# GSM.net
KiCad netlist of a schematic drawn in Altium Designer
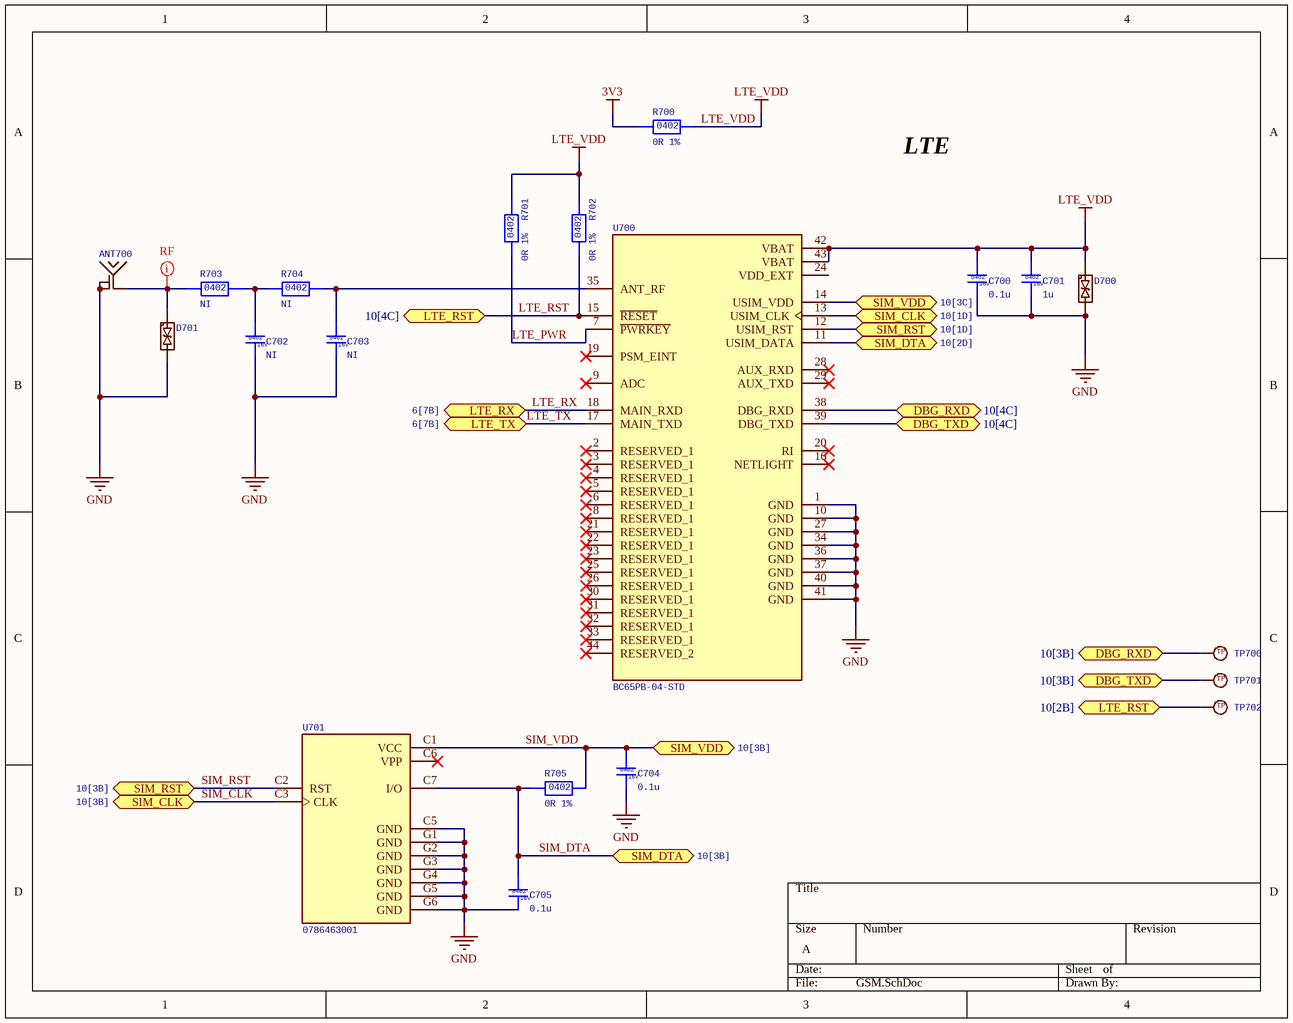
[diagram p0: GSM.SchDoc]

(export (version "E")
  (design (tool "Eeschema 10.0.6"))
  (components
    (comp (ref "ANT700")
      (value "2337019-1")
      (footprint "2337019-1")
      (description "UMCC MICRO-COAX RECEPTACLE, GEN")
      (libsource (lib "Hw_Lib") (part "2337019-1"))
    )
    (comp (ref "C700")
      (value "0.1u")
      (footprint "CAP0402")
      (fields
        (field (name "MANUFACTURER") "Murata")
        (field (name "MANUFACTURER PART NUMBER") "GRM155R71C104KA88J")
      )
      (libsource (lib "Hw_Lib") (part "C_0402_0.1u"))
    )
    (comp (ref "C701")
      (value "1u")
      (footprint "CAP0402")
      (fields
        (field (name "MANUFACTURER") "Taiyo Yuden")
        (field (name "MANUFACTURER PART NUMBER") "EMK105BJ105KV-F")
      )
      (libsource (lib "Hw_Lib") (part "C_0402_1u"))
    )
    (comp (ref "C702")
      (value "NI")
      (footprint "CAP0402")
      (fields
        (field (name "MANUFACTURER") "Murata")
        (field (name "MANUFACTURER PART NUMBER") "GRM155R71C104KA88J")
      )
      (libsource (lib "Hw_Lib") (part "C_0402_0.1u"))
    )
    (comp (ref "C703")
      (value "NI")
      (footprint "CAP0402")
      (fields
        (field (name "MANUFACTURER") "Murata")
        (field (name "MANUFACTURER PART NUMBER") "GRM155R71C104KA88J")
      )
      (libsource (lib "Hw_Lib") (part "C_0402_0.1u"))
    )
    (comp (ref "C704")
      (value "0.1u")
      (footprint "CAP0402")
      (fields
        (field (name "MANUFACTURER") "Murata")
        (field (name "MANUFACTURER PART NUMBER") "GRM155R71C104KA88J")
      )
      (libsource (lib "Hw_Lib") (part "C_0402_0.1u"))
    )
    (comp (ref "C705")
      (value "0.1u")
      (footprint "CAP0402")
      (fields
        (field (name "MANUFACTURER") "Murata")
        (field (name "MANUFACTURER PART NUMBER") "GRM155R71C104KA88J")
      )
      (libsource (lib "Hw_Lib") (part "C_0402_0.1u"))
    )
    (comp (ref "D700")
      (value "DESD3V3S1BL-7B")
      (footprint "DESD3V3S1BL-7B")
      (description "Trans Voltage Suppressor Diode, 35W, 3.3V V(RWM), Bidirectional, 1 Element, Silicon")
      (fields (field (name "MANUFACTURER") "Diodes"))
      (libsource (lib "Hw_Lib") (part "DESD3V3S1BL-7B"))
    )
    (comp (ref "D701")
      (value "DESD3V3S1BL-7B")
      (footprint "DESD3V3S1BL-7B")
      (description "Trans Voltage Suppressor Diode, 35W, 3.3V V(RWM), Bidirectional, 1 Element, Silicon")
      (fields (field (name "MANUFACTURER") "Diodes"))
      (libsource (lib "Hw_Lib") (part "DESD3V3S1BL-7B"))
    )
    (comp (ref "R700")
      (value "0R 1%")
      (footprint "RES0402")
      (description "Metal Glaze/thick Film, 0.0625W, 0ohm, Surface Mount, 0402")
      (fields
        (field (name "MANUFACTURER") "Yageo")
        (field (name "MANUFACTURER PART NUMBER") "RC0402JR-070RL")
      )
      (libsource (lib "Hw_Lib") (part "R_0402_0R"))
    )
    (comp (ref "R701")
      (value "0R 1%")
      (footprint "RES0402")
      (description "Metal Glaze/thick Film, 0.0625W, 0ohm, Surface Mount, 0402")
      (fields
        (field (name "MANUFACTURER") "Yageo")
        (field (name "MANUFACTURER PART NUMBER") "RC0402JR-070RL")
      )
      (libsource (lib "Hw_Lib") (part "R_0402_0R"))
    )
    (comp (ref "R702")
      (value "0R 1%")
      (footprint "RES0402")
      (description "Metal Glaze/thick Film, 0.0625W, 0ohm, Surface Mount, 0402")
      (fields
        (field (name "MANUFACTURER") "Yageo")
        (field (name "MANUFACTURER PART NUMBER") "RC0402JR-070RL")
      )
      (libsource (lib "Hw_Lib") (part "R_0402_0R"))
    )
    (comp (ref "R703")
      (value "NI")
      (footprint "RES0402")
      (description "Metal Glaze/thick Film, 0.0625W, 0ohm, Surface Mount, 0402")
      (fields
        (field (name "MANUFACTURER") "Yageo")
        (field (name "MANUFACTURER PART NUMBER") "RC0402JR-070RL")
      )
      (libsource (lib "Hw_Lib") (part "R_0402_0R"))
    )
    (comp (ref "R704")
      (value "NI")
      (footprint "RES0402")
      (description "Metal Glaze/thick Film, 0.0625W, 0ohm, Surface Mount, 0402")
      (fields
        (field (name "MANUFACTURER") "Yageo")
        (field (name "MANUFACTURER PART NUMBER") "RC0402JR-070RL")
      )
      (libsource (lib "Hw_Lib") (part "R_0402_0R"))
    )
    (comp (ref "R705")
      (value "0R 1%")
      (footprint "RES0402")
      (description "Metal Glaze/thick Film, 0.0625W, 0ohm, Surface Mount, 0402")
      (fields
        (field (name "MANUFACTURER") "Yageo")
        (field (name "MANUFACTURER PART NUMBER") "RC0402JR-070RL")
      )
      (libsource (lib "Hw_Lib") (part "R_0402_0R"))
    )
    (comp (ref "TP700")
      (value "TP")
      (footprint "TP")
      (description "Test Point")
      (libsource (lib "Hw_Lib") (part "TP"))
    )
    (comp (ref "TP701")
      (value "TP")
      (footprint "TP")
      (description "Test Point")
      (libsource (lib "Hw_Lib") (part "TP"))
    )
    (comp (ref "TP702")
      (value "TP")
      (footprint "TP")
      (description "Test Point")
      (libsource (lib "Hw_Lib") (part "TP"))
    )
    (comp (ref "U700")
      (value "BC65PB-04-STD")
      (footprint "BC65PB-04-STD")
      (fields (field (name "MANUFACTURER") "Quectel Wireless Solutions"))
      (libsource (lib "Hw_Lib") (part "BC65PB-04-STD"))
    )
    (comp (ref "U701")
      (value "0786463001")
      (footprint "0786463001")
      (description "PCB Connector")
      (fields (field (name "MANUFACTURER") "Molex"))
      (libsource (lib "Hw_Lib") (part "0786463001"))
    )
  )
  (nets
    (net (code "1") (name "/DBG_RXD") (class "Default")
      (node (ref "TP700") (pin "1") (pinfunction "1_1") (pintype "passive"))
      (node (ref "U700") (pin "38") (pinfunction "DBG_RXD_38") (pintype "open_collector"))
    )
    (net (code "2") (name "/DBG_TXD") (class "Default")
      (node (ref "TP701") (pin "1") (pinfunction "1_1") (pintype "passive"))
      (node (ref "U700") (pin "39") (pinfunction "DBG_TXD_39") (pintype "open_collector"))
    )
    (net (code "3") (name "/LTE_PWR") (class "Default")
      (node (ref "R701") (pin "1") (pinfunction "1_1") (pintype "passive"))
      (node (ref "U700") (pin "7") (pinfunction "~{PWRKEY}_7") (pintype "open_collector"))
    )
    (net (code "4") (name "/LTE_RST") (class "Default")
      (node (ref "R702") (pin "1") (pinfunction "1_1") (pintype "passive"))
      (node (ref "TP702") (pin "1") (pinfunction "1_1") (pintype "passive"))
      (node (ref "U700") (pin "15") (pinfunction "~{RESET}_15") (pintype "open_collector"))
    )
    (net (code "5") (name "/LTE_RX") (class "Default")
      (node (ref "U700") (pin "18") (pinfunction "MAIN_RXD_18") (pintype "open_collector"))
    )
    (net (code "6") (name "/LTE_TX") (class "Default")
      (node (ref "U700") (pin "17") (pinfunction "MAIN_TXD_17") (pintype "open_collector"))
    )
    (net (code "7") (name "/SIM_CLK") (class "Default")
      (node (ref "U700") (pin "13") (pinfunction "USIM_CLK_13") (pintype "open_collector"))
      (node (ref "U701") (pin "C3") (pinfunction "CLK_C3") (pintype "open_collector"))
    )
    (net (code "8") (name "/SIM_DTA") (class "Default")
      (node (ref "C705") (pin "1") (pinfunction "1_1") (pintype "passive"))
      (node (ref "R705") (pin "1") (pinfunction "1_1") (pintype "passive"))
      (node (ref "U700") (pin "11") (pinfunction "USIM_DATA_11") (pintype "open_collector"))
      (node (ref "U701") (pin "C7") (pinfunction "I/O_C7") (pintype "open_collector"))
    )
    (net (code "9") (name "/SIM_RST") (class "Default")
      (node (ref "U700") (pin "12") (pinfunction "USIM_RST_12") (pintype "open_collector"))
      (node (ref "U701") (pin "C2") (pinfunction "RST_C2") (pintype "open_collector"))
    )
    (net (code "10") (name "/SIM_VDD") (class "Default")
      (node (ref "C704") (pin "1") (pinfunction "1_1") (pintype "passive"))
      (node (ref "R705") (pin "2") (pinfunction "2_2") (pintype "passive"))
      (node (ref "U700") (pin "14") (pinfunction "USIM_VDD_14") (pintype "open_collector"))
      (node (ref "U701") (pin "C1") (pinfunction "VCC_C1") (pintype "open_collector"))
    )
    (net (code "11") (name "3V3") (class "Default")
      (node (ref "R700") (pin "1") (pinfunction "1_1") (pintype "passive"))
    )
    (net (code "12") (name "GND") (class "Default")
      (node (ref "ANT700") (pin "G1") (pinfunction "GND_G1") (pintype "open_collector"))
      (node (ref "ANT700") (pin "G2") (pinfunction "GND_G2") (pintype "open_collector"))
      (node (ref "C700") (pin "2") (pinfunction "2_2") (pintype "passive"))
      (node (ref "C701") (pin "2") (pinfunction "2_2") (pintype "passive"))
      (node (ref "C702") (pin "2") (pinfunction "2_2") (pintype "passive"))
      (node (ref "C703") (pin "2") (pinfunction "2_2") (pintype "passive"))
      (node (ref "C704") (pin "2") (pinfunction "2_2") (pintype "passive"))
      (node (ref "C705") (pin "2") (pinfunction "2_2") (pintype "passive"))
      (node (ref "D700") (pin "2") (pinfunction "2_2") (pintype "passive"))
      (node (ref "D701") (pin "2") (pinfunction "2_2") (pintype "passive"))
      (node (ref "U700") (pin "1") (pinfunction "GND_1") (pintype "open_collector"))
      (node (ref "U700") (pin "10") (pinfunction "GND_10") (pintype "open_collector"))
      (node (ref "U700") (pin "27") (pinfunction "GND_27") (pintype "open_collector"))
      (node (ref "U700") (pin "34") (pinfunction "GND_34") (pintype "open_collector"))
      (node (ref "U700") (pin "36") (pinfunction "GND_36") (pintype "open_collector"))
      (node (ref "U700") (pin "37") (pinfunction "GND_37") (pintype "open_collector"))
      (node (ref "U700") (pin "40") (pinfunction "GND_40") (pintype "open_collector"))
      (node (ref "U700") (pin "41") (pinfunction "GND_41") (pintype "open_collector"))
      (node (ref "U701") (pin "C5") (pinfunction "GND_C5") (pintype "open_collector"))
      (node (ref "U701") (pin "G1") (pinfunction "GND_G1") (pintype "open_collector"))
      (node (ref "U701") (pin "G2") (pinfunction "GND_G2") (pintype "open_collector"))
      (node (ref "U701") (pin "G3") (pinfunction "GND_G3") (pintype "open_collector"))
      (node (ref "U701") (pin "G4") (pinfunction "GND_G4") (pintype "open_collector"))
      (node (ref "U701") (pin "G5") (pinfunction "GND_G5") (pintype "open_collector"))
      (node (ref "U701") (pin "G6") (pinfunction "GND_G6") (pintype "open_collector"))
    )
    (net (code "13") (name "LTE_VDD") (class "Default")
      (node (ref "C700") (pin "1") (pinfunction "1_1") (pintype "passive"))
      (node (ref "C701") (pin "1") (pinfunction "1_1") (pintype "passive"))
      (node (ref "D700") (pin "1") (pinfunction "1_1") (pintype "passive"))
      (node (ref "R700") (pin "2") (pinfunction "2_2") (pintype "passive"))
      (node (ref "R701") (pin "2") (pinfunction "2_2") (pintype "passive"))
      (node (ref "R702") (pin "2") (pinfunction "2_2") (pintype "passive"))
      (node (ref "U700") (pin "42") (pinfunction "VBAT_42") (pintype "open_collector"))
      (node (ref "U700") (pin "43") (pinfunction "VBAT_43") (pintype "open_collector"))
    )
    (net (code "14") (name "Net-(ANT700-Pad1)") (class "Default")
      (node (ref "ANT700") (pin "1") (pinfunction "1_1") (pintype "passive"))
      (node (ref "D701") (pin "1") (pinfunction "1_1") (pintype "passive"))
      (node (ref "R703") (pin "1") (pinfunction "1_1") (pintype "passive"))
    )
    (net (code "15") (name "Net-(C702-Pad1)") (class "Default")
      (node (ref "C702") (pin "1") (pinfunction "1_1") (pintype "passive"))
      (node (ref "R703") (pin "2") (pinfunction "2_2") (pintype "passive"))
      (node (ref "R704") (pin "1") (pinfunction "1_1") (pintype "passive"))
    )
    (net (code "16") (name "Net-(U700-ANT_RF)") (class "Default")
      (node (ref "C703") (pin "1") (pinfunction "1_1") (pintype "passive"))
      (node (ref "R704") (pin "2") (pinfunction "2_2") (pintype "passive"))
      (node (ref "U700") (pin "35") (pinfunction "ANT_RF_35") (pintype "open_collector"))
    )
    (net (code "17") (name "unconnected-(U700-ADC-Pad9)") (class "Default")
      (node (ref "U700") (pin "9") (pinfunction "ADC_9") (pintype "open_collector+no_connect"))
    )
    (net (code "18") (name "unconnected-(U700-AUX_RXD-Pad28)") (class "Default")
      (node (ref "U700") (pin "28") (pinfunction "AUX_RXD_28") (pintype "open_collector+no_connect"))
    )
    (net (code "19") (name "unconnected-(U700-AUX_TXD-Pad29)") (class "Default")
      (node (ref "U700") (pin "29") (pinfunction "AUX_TXD_29") (pintype "open_collector+no_connect"))
    )
    (net (code "20") (name "unconnected-(U700-NETLIGHT-Pad16)") (class "Default")
      (node (ref "U700") (pin "16") (pinfunction "NETLIGHT_16") (pintype "open_collector+no_connect"))
    )
    (net (code "21") (name "unconnected-(U700-PSM_EINT-Pad19)") (class "Default")
      (node (ref "U700") (pin "19") (pinfunction "PSM_EINT_19") (pintype "open_collector+no_connect"))
    )
    (net (code "22") (name "unconnected-(U700-RESERVED_1-Pad2)") (class "Default")
      (node (ref "U700") (pin "2") (pinfunction "RESERVED_1_2") (pintype "open_collector+no_connect"))
    )
    (net (code "23") (name "unconnected-(U700-RESERVED_1-Pad3)") (class "Default")
      (node (ref "U700") (pin "3") (pinfunction "RESERVED_1_3") (pintype "open_collector+no_connect"))
    )
    (net (code "24") (name "unconnected-(U700-RESERVED_1-Pad4)") (class "Default")
      (node (ref "U700") (pin "4") (pinfunction "RESERVED_1_4") (pintype "open_collector+no_connect"))
    )
    (net (code "25") (name "unconnected-(U700-RESERVED_1-Pad5)") (class "Default")
      (node (ref "U700") (pin "5") (pinfunction "RESERVED_1_5") (pintype "open_collector+no_connect"))
    )
    (net (code "26") (name "unconnected-(U700-RESERVED_1-Pad6)") (class "Default")
      (node (ref "U700") (pin "6") (pinfunction "RESERVED_1_6") (pintype "open_collector+no_connect"))
    )
    (net (code "27") (name "unconnected-(U700-RESERVED_1-Pad8)") (class "Default")
      (node (ref "U700") (pin "8") (pinfunction "RESERVED_1_8") (pintype "open_collector+no_connect"))
    )
    (net (code "28") (name "unconnected-(U700-RESERVED_1-Pad21)") (class "Default")
      (node (ref "U700") (pin "21") (pinfunction "RESERVED_1_21") (pintype "open_collector+no_connect"))
    )
    (net (code "29") (name "unconnected-(U700-RESERVED_1-Pad22)") (class "Default")
      (node (ref "U700") (pin "22") (pinfunction "RESERVED_1_22") (pintype "open_collector+no_connect"))
    )
    (net (code "30") (name "unconnected-(U700-RESERVED_1-Pad23)") (class "Default")
      (node (ref "U700") (pin "23") (pinfunction "RESERVED_1_23") (pintype "open_collector+no_connect"))
    )
    (net (code "31") (name "unconnected-(U700-RESERVED_1-Pad25)") (class "Default")
      (node (ref "U700") (pin "25") (pinfunction "RESERVED_1_25") (pintype "open_collector+no_connect"))
    )
    (net (code "32") (name "unconnected-(U700-RESERVED_1-Pad26)") (class "Default")
      (node (ref "U700") (pin "26") (pinfunction "RESERVED_1_26") (pintype "open_collector+no_connect"))
    )
    (net (code "33") (name "unconnected-(U700-RESERVED_1-Pad30)") (class "Default")
      (node (ref "U700") (pin "30") (pinfunction "RESERVED_1_30") (pintype "open_collector+no_connect"))
    )
    (net (code "34") (name "unconnected-(U700-RESERVED_1-Pad31)") (class "Default")
      (node (ref "U700") (pin "31") (pinfunction "RESERVED_1_31") (pintype "open_collector+no_connect"))
    )
    (net (code "35") (name "unconnected-(U700-RESERVED_1-Pad32)") (class "Default")
      (node (ref "U700") (pin "32") (pinfunction "RESERVED_1_32") (pintype "open_collector+no_connect"))
    )
    (net (code "36") (name "unconnected-(U700-RESERVED_1-Pad33)") (class "Default")
      (node (ref "U700") (pin "33") (pinfunction "RESERVED_1_33") (pintype "open_collector+no_connect"))
    )
    (net (code "37") (name "unconnected-(U700-RESERVED_2-Pad44)") (class "Default")
      (node (ref "U700") (pin "44") (pinfunction "RESERVED_2_44") (pintype "open_collector+no_connect"))
    )
    (net (code "38") (name "unconnected-(U700-RI-Pad20)") (class "Default")
      (node (ref "U700") (pin "20") (pinfunction "RI_20") (pintype "open_collector+no_connect"))
    )
    (net (code "39") (name "unconnected-(U700-VDD_EXT-Pad24)") (class "Default")
      (node (ref "U700") (pin "24") (pinfunction "VDD_EXT_24") (pintype "open_collector"))
    )
    (net (code "40") (name "unconnected-(U701-VPP-PadC6)") (class "Default")
      (node (ref "U701") (pin "C6") (pinfunction "VPP_C6") (pintype "open_collector+no_connect"))
    )
  )
)
